# usbtiny-v2-SS.net
KiCad netlist of a schematic drawn in EAGLE
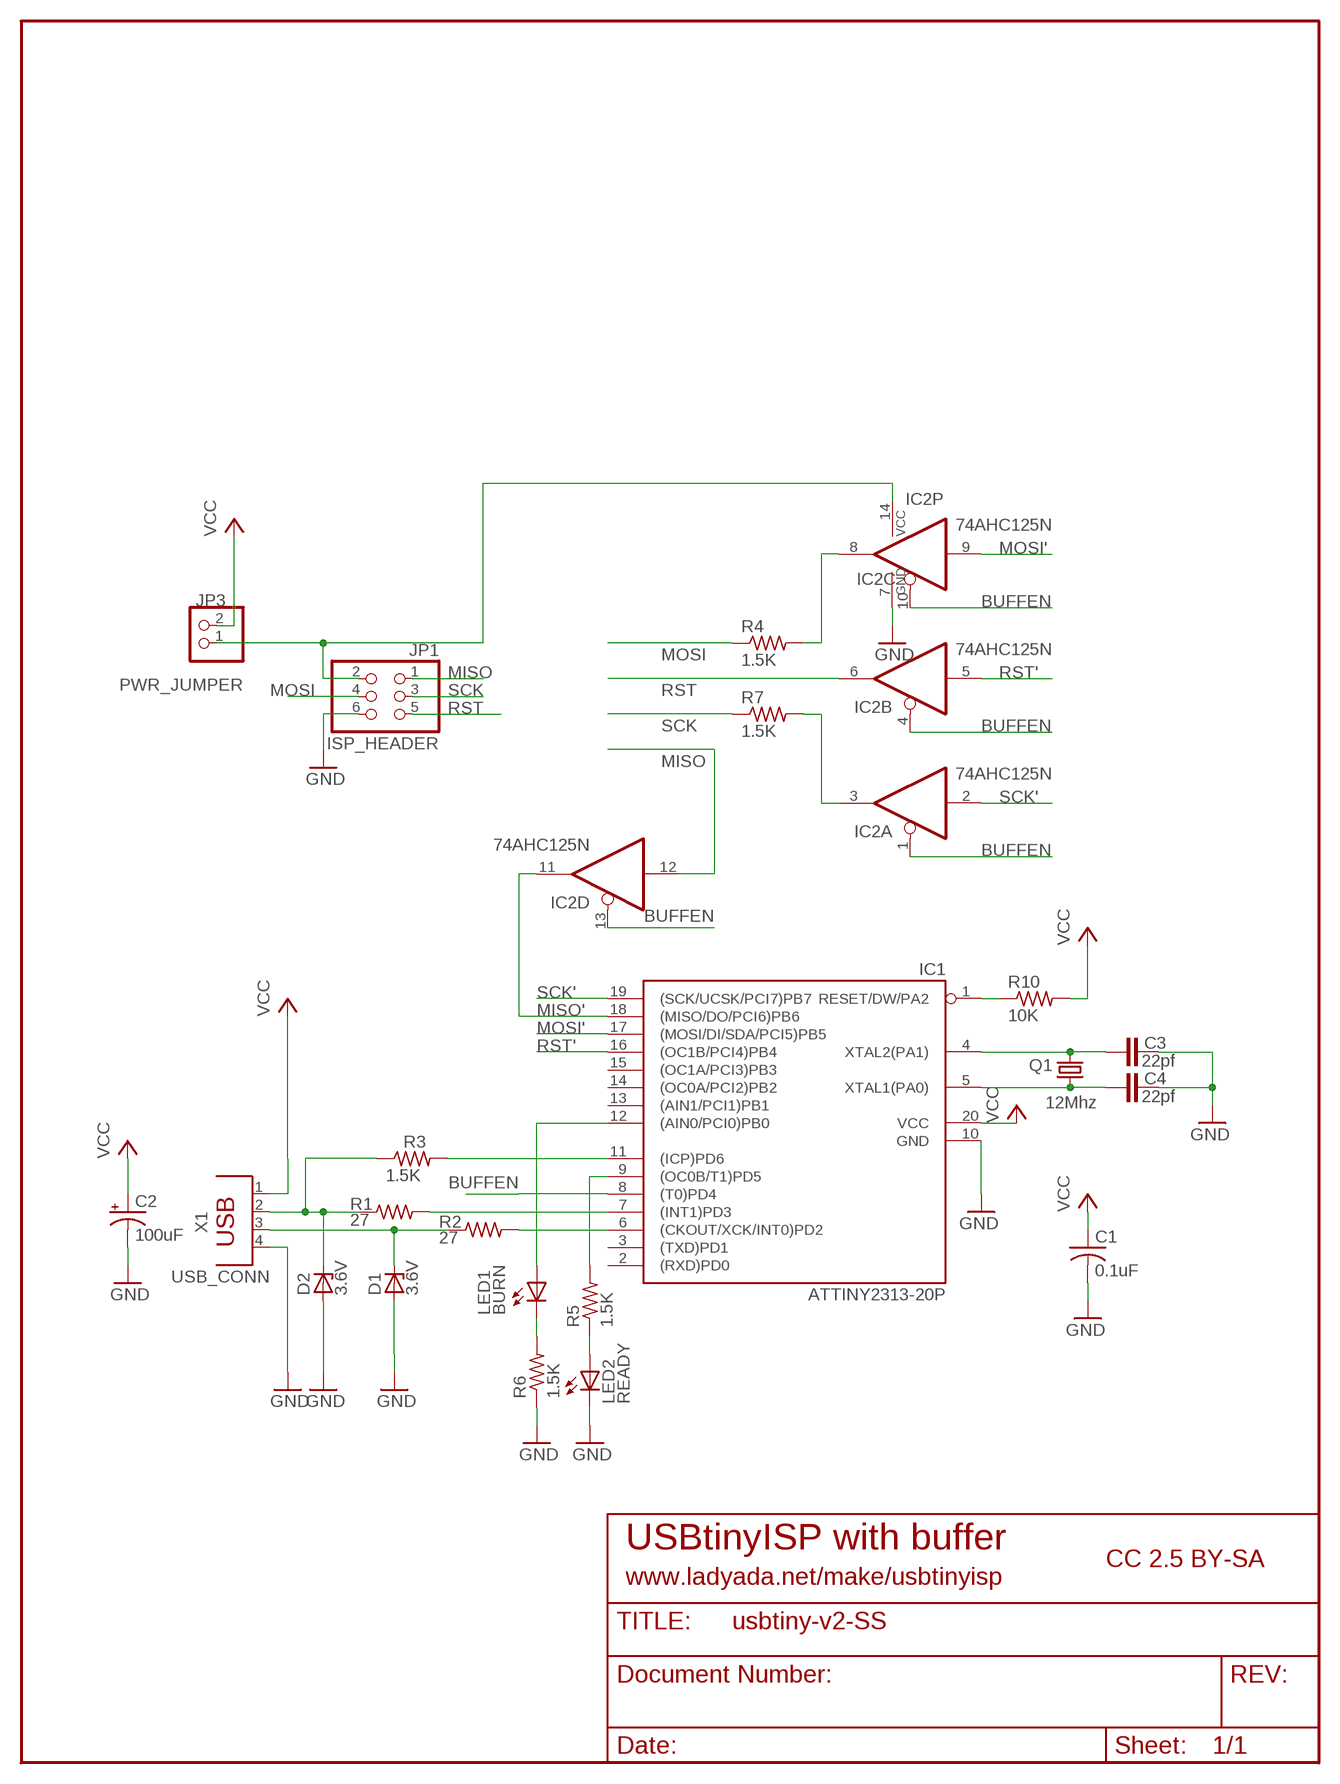
[diagram p0: schematic, sheet 1]

(export (version "E")
  (design (tool "Eeschema 10.0.6"))
  (components
    (comp (ref "C1")
      (value "0.1uF")
      (footprint "eagle-import:C025-025X050")
      (libsource (lib "eagle-import") (part "C-US025-025X050"))
    )
    (comp (ref "C2")
      (value "100uF")
      (footprint "eagle-import:E2,5-5")
      (libsource (lib "eagle-import") (part "CPOL-USE2.5-5"))
    )
    (comp (ref "C3")
      (value "22pf")
      (footprint "eagle-import:C025-025X050")
      (libsource (lib "eagle-import") (part "C-EU025-025X050"))
    )
    (comp (ref "C4")
      (value "22pf")
      (footprint "eagle-import:C025-025X050")
      (libsource (lib "eagle-import") (part "C-EU025-025X050"))
    )
    (comp (ref "D1")
      (value "3.6V")
      (footprint "eagle-import:DO35Z10")
      (libsource (lib "eagle-import") (part "ZENER-DIODEDO35Z10"))
    )
    (comp (ref "D2")
      (value "3.6V")
      (footprint "eagle-import:DO35Z10")
      (libsource (lib "eagle-import") (part "ZENER-DIODEDO35Z10"))
    )
    (comp (ref "IC1")
      (value "ATTINY2313-20P")
      (footprint "eagle-import:DIL20")
      (libsource (lib "eagle-import") (part "ATTINY2313P-20"))
    )
    (comp (ref "IC2")
      (value "74AHC125N")
      (footprint "eagle-import:DIL14")
      (libsource (lib "eagle-import") (part "74125NHC"))
    )
    (comp (ref "JP1")
      (value "ISP_HEADER")
      (footprint "eagle-import:2X03")
      (libsource (lib "eagle-import") (part "PINHD-2X3"))
    )
    (comp (ref "JP3")
      (value "PWR_JUMPER")
      (footprint "eagle-import:1X02")
      (libsource (lib "eagle-import") (part "PINHD-1X2"))
    )
    (comp (ref "LED1")
      (value "BURN")
      (footprint "eagle-import:LED3MM")
      (libsource (lib "eagle-import") (part "LED3MM"))
    )
    (comp (ref "LED2")
      (value "READY")
      (footprint "eagle-import:LED3MM")
      (libsource (lib "eagle-import") (part "LED3MM"))
    )
    (comp (ref "Q1")
      (value "12Mhz")
      (footprint "eagle-import:HC49_S")
      (libsource (lib "eagle-import") (part "CRYSTALHC49S"))
    )
    (comp (ref "R1")
      (value "27")
      (footprint "eagle-import:0207_10")
      (libsource (lib "eagle-import") (part "R-US_0207/10"))
    )
    (comp (ref "R2")
      (value "27")
      (footprint "eagle-import:0207_10")
      (libsource (lib "eagle-import") (part "R-US_0207/10"))
    )
    (comp (ref "R3")
      (value "1.5K")
      (footprint "eagle-import:0207_10")
      (libsource (lib "eagle-import") (part "R-US_0207/10"))
    )
    (comp (ref "R4")
      (value "1.5K")
      (footprint "eagle-import:0207_10")
      (libsource (lib "eagle-import") (part "R-US_0207/10"))
    )
    (comp (ref "R5")
      (value "1.5K")
      (footprint "eagle-import:0207_2V")
      (libsource (lib "eagle-import") (part "R-US_0207/2V"))
    )
    (comp (ref "R6")
      (value "1.5K")
      (footprint "eagle-import:0207_2V")
      (libsource (lib "eagle-import") (part "R-US_0207/2V"))
    )
    (comp (ref "R7")
      (value "1.5K")
      (footprint "eagle-import:0207_10")
      (libsource (lib "eagle-import") (part "R-US_0207/10"))
    )
    (comp (ref "R10")
      (value "10K")
      (footprint "eagle-import:0207_10")
      (libsource (lib "eagle-import") (part "R-US_0207/10"))
    )
    (comp (ref "X1")
      (value "USB_CONN")
      (footprint "eagle-import:PN61729")
      (libsource (lib "eagle-import") (part "PN61729"))
    )
  )
  (nets
    (net (code "1") (name "/BUFFEN") (class "Default")
      (node (ref "IC1") (pin "8") (pinfunction "(T0)PD4_8") (pintype "bidirectional"))
      (node (ref "IC2") (pin "1") (pinfunction "OE_1") (pintype "input"))
      (node (ref "IC2") (pin "10") (pinfunction "OE_10") (pintype "input"))
      (node (ref "IC2") (pin "13") (pinfunction "OE_13") (pintype "input"))
      (node (ref "IC2") (pin "4") (pinfunction "OE_4") (pintype "input"))
    )
    (net (code "2") (name "/MISO") (class "Default")
      (node (ref "IC2") (pin "12") (pinfunction "I_12") (pintype "input"))
      (node (ref "JP1") (pin "1") (pinfunction "1_1") (pintype "passive"))
    )
    (net (code "3") (name "/MISO'") (class "Default")
      (node (ref "IC1") (pin "18") (pinfunction "(MISO/DO/PCI6)PB6_18") (pintype "bidirectional"))
      (node (ref "IC2") (pin "11") (pinfunction "O_11") (pintype "tri_state"))
    )
    (net (code "4") (name "/MOSI") (class "Default")
      (node (ref "JP1") (pin "4") (pinfunction "4_4") (pintype "passive"))
      (node (ref "R4") (pin "1") (pinfunction "1_1") (pintype "passive"))
    )
    (net (code "5") (name "/MOSI'") (class "Default")
      (node (ref "IC1") (pin "17") (pinfunction "(MOSI/DI/SDA/PCI5)PB5_17") (pintype "bidirectional"))
      (node (ref "IC2") (pin "9") (pinfunction "I_9") (pintype "input"))
    )
    (net (code "6") (name "/RST") (class "Default")
      (node (ref "IC2") (pin "6") (pinfunction "O_6") (pintype "tri_state"))
      (node (ref "JP1") (pin "5") (pinfunction "5_5") (pintype "passive"))
    )
    (net (code "7") (name "/RST'") (class "Default")
      (node (ref "IC1") (pin "16") (pinfunction "(OC1B/PCI4)PB4_16") (pintype "bidirectional"))
      (node (ref "IC2") (pin "5") (pinfunction "I_5") (pintype "input"))
    )
    (net (code "8") (name "/SCK") (class "Default")
      (node (ref "JP1") (pin "3") (pinfunction "3_3") (pintype "passive"))
      (node (ref "R7") (pin "1") (pinfunction "1_1") (pintype "passive"))
    )
    (net (code "9") (name "/SCK'") (class "Default")
      (node (ref "IC1") (pin "19") (pinfunction "(SCK/UCSK/PCI7)PB7_19") (pintype "bidirectional"))
      (node (ref "IC2") (pin "2") (pinfunction "I_2") (pintype "input"))
    )
    (net (code "10") (name "GND") (class "Default")
      (node (ref "C1") (pin "2") (pinfunction "2_2") (pintype "passive"))
      (node (ref "C2") (pin "-") (pinfunction "-_-") (pintype "passive"))
      (node (ref "C3") (pin "2") (pinfunction "2_2") (pintype "passive"))
      (node (ref "C4") (pin "2") (pinfunction "2_2") (pintype "passive"))
      (node (ref "D1") (pin "A") (pinfunction "A_A") (pintype "passive"))
      (node (ref "D2") (pin "A") (pinfunction "A_A") (pintype "passive"))
      (node (ref "IC1") (pin "10") (pinfunction "GND_10") (pintype "power_in"))
      (node (ref "IC2") (pin "7") (pinfunction "GND_7") (pintype "power_in"))
      (node (ref "JP1") (pin "6") (pinfunction "6_6") (pintype "passive"))
      (node (ref "LED2") (pin "K") (pinfunction "C_K") (pintype "passive"))
      (node (ref "R6") (pin "1") (pinfunction "1_1") (pintype "passive"))
      (node (ref "X1") (pin "4") (pinfunction "4_4") (pintype "bidirectional"))
    )
    (net (code "11") (name "Net-(D1-PadC)") (class "Default")
      (node (ref "D1") (pin "C") (pinfunction "C_C") (pintype "passive"))
      (node (ref "R2") (pin "1") (pinfunction "1_1") (pintype "passive"))
      (node (ref "X1") (pin "3") (pinfunction "3_3") (pintype "bidirectional"))
    )
    (net (code "12") (name "Net-(D2-PadC)") (class "Default")
      (node (ref "D2") (pin "C") (pinfunction "C_C") (pintype "passive"))
      (node (ref "R1") (pin "1") (pinfunction "1_1") (pintype "passive"))
      (node (ref "R3") (pin "1") (pinfunction "1_1") (pintype "passive"))
      (node (ref "X1") (pin "2") (pinfunction "2_2") (pintype "bidirectional"))
    )
    (net (code "13") (name "Net-(IC1-(AIN0{slash}PCI0)PB0)") (class "Default")
      (node (ref "IC1") (pin "12") (pinfunction "(AIN0/PCI0)PB0_12") (pintype "bidirectional"))
      (node (ref "LED1") (pin "A") (pinfunction "A_A") (pintype "passive"))
    )
    (net (code "14") (name "Net-(IC1-(CKOUT{slash}XCK{slash}INT0)PD2)") (class "Default")
      (node (ref "IC1") (pin "6") (pinfunction "(CKOUT/XCK/INT0)PD2_6") (pintype "bidirectional"))
      (node (ref "R2") (pin "2") (pinfunction "2_2") (pintype "passive"))
    )
    (net (code "15") (name "Net-(IC1-(ICP)PD6)") (class "Default")
      (node (ref "IC1") (pin "11") (pinfunction "(ICP)PD6_11") (pintype "bidirectional"))
      (node (ref "R3") (pin "2") (pinfunction "2_2") (pintype "passive"))
    )
    (net (code "16") (name "Net-(IC1-(INT1)PD3)") (class "Default")
      (node (ref "IC1") (pin "7") (pinfunction "(INT1)PD3_7") (pintype "bidirectional"))
      (node (ref "R1") (pin "2") (pinfunction "2_2") (pintype "passive"))
    )
    (net (code "17") (name "Net-(IC1-(OC0B{slash}T1)PD5)") (class "Default")
      (node (ref "IC1") (pin "9") (pinfunction "(OC0B/T1)PD5_9") (pintype "bidirectional"))
      (node (ref "R5") (pin "2") (pinfunction "2_2") (pintype "passive"))
    )
    (net (code "18") (name "Net-(IC1-RESET{slash}DW{slash}PA2)") (class "Default")
      (node (ref "IC1") (pin "1") (pinfunction "RESET/DW/PA2_1") (pintype "bidirectional"))
      (node (ref "R10") (pin "1") (pinfunction "1_1") (pintype "passive"))
    )
    (net (code "19") (name "Net-(IC1-XTAL1(PA0))") (class "Default")
      (node (ref "C4") (pin "1") (pinfunction "1_1") (pintype "passive"))
      (node (ref "IC1") (pin "5") (pinfunction "XTAL1(PA0)_5") (pintype "bidirectional"))
      (node (ref "Q1") (pin "1") (pinfunction "1_1") (pintype "passive"))
    )
    (net (code "20") (name "Net-(IC1-XTAL2(PA1))") (class "Default")
      (node (ref "C3") (pin "1") (pinfunction "1_1") (pintype "passive"))
      (node (ref "IC1") (pin "4") (pinfunction "XTAL2(PA1)_4") (pintype "bidirectional"))
      (node (ref "Q1") (pin "2") (pinfunction "2_2") (pintype "passive"))
    )
    (net (code "21") (name "Net-(IC2A-O)") (class "Default")
      (node (ref "IC2") (pin "3") (pinfunction "O_3") (pintype "tri_state"))
      (node (ref "R7") (pin "2") (pinfunction "2_2") (pintype "passive"))
    )
    (net (code "22") (name "Net-(IC2C-O)") (class "Default")
      (node (ref "IC2") (pin "8") (pinfunction "O_8") (pintype "tri_state"))
      (node (ref "R4") (pin "2") (pinfunction "2_2") (pintype "passive"))
    )
    (net (code "23") (name "Net-(IC2E-VCC)") (class "Default")
      (node (ref "IC2") (pin "14") (pinfunction "VCC_14") (pintype "power_in"))
      (node (ref "JP1") (pin "2") (pinfunction "2_2") (pintype "passive"))
      (node (ref "JP3") (pin "1") (pinfunction "1_1") (pintype "passive"))
    )
    (net (code "24") (name "Net-(LED1-C)") (class "Default")
      (node (ref "LED1") (pin "K") (pinfunction "C_K") (pintype "passive"))
      (node (ref "R6") (pin "2") (pinfunction "2_2") (pintype "passive"))
    )
    (net (code "25") (name "Net-(LED2-PadA)") (class "Default")
      (node (ref "LED2") (pin "A") (pinfunction "A_A") (pintype "passive"))
      (node (ref "R5") (pin "1") (pinfunction "1_1") (pintype "passive"))
    )
    (net (code "26") (name "VCC") (class "Default")
      (node (ref "C1") (pin "1") (pinfunction "1_1") (pintype "passive"))
      (node (ref "C2") (pin "+") (pinfunction "+_+") (pintype "passive"))
      (node (ref "IC1") (pin "20") (pinfunction "VCC_20") (pintype "power_in"))
      (node (ref "JP3") (pin "2") (pinfunction "2_2") (pintype "passive"))
      (node (ref "R10") (pin "2") (pinfunction "2_2") (pintype "passive"))
      (node (ref "X1") (pin "1") (pinfunction "1_1") (pintype "bidirectional"))
    )
    (net (code "27") (name "unconnected-(IC1-(AIN1{slash}PCI1)PB1-Pad13)") (class "Default")
      (node (ref "IC1") (pin "13") (pinfunction "(AIN1/PCI1)PB1_13") (pintype "bidirectional"))
    )
    (net (code "28") (name "unconnected-(IC1-(OC0A{slash}PCI2)PB2-Pad14)") (class "Default")
      (node (ref "IC1") (pin "14") (pinfunction "(OC0A/PCI2)PB2_14") (pintype "bidirectional"))
    )
    (net (code "29") (name "unconnected-(IC1-(OC1A{slash}PCI3)PB3-Pad15)") (class "Default")
      (node (ref "IC1") (pin "15") (pinfunction "(OC1A/PCI3)PB3_15") (pintype "bidirectional"))
    )
    (net (code "30") (name "unconnected-(IC1-(RXD)PD0-Pad2)") (class "Default")
      (node (ref "IC1") (pin "2") (pinfunction "(RXD)PD0_2") (pintype "bidirectional"))
    )
    (net (code "31") (name "unconnected-(IC1-(TXD)PD1-Pad3)") (class "Default")
      (node (ref "IC1") (pin "3") (pinfunction "(TXD)PD1_3") (pintype "bidirectional"))
    )
  )
)
